# ramanPi_imagingBoard_ccdBoard.net
KiCad netlist of a schematic drawn in EAGLE
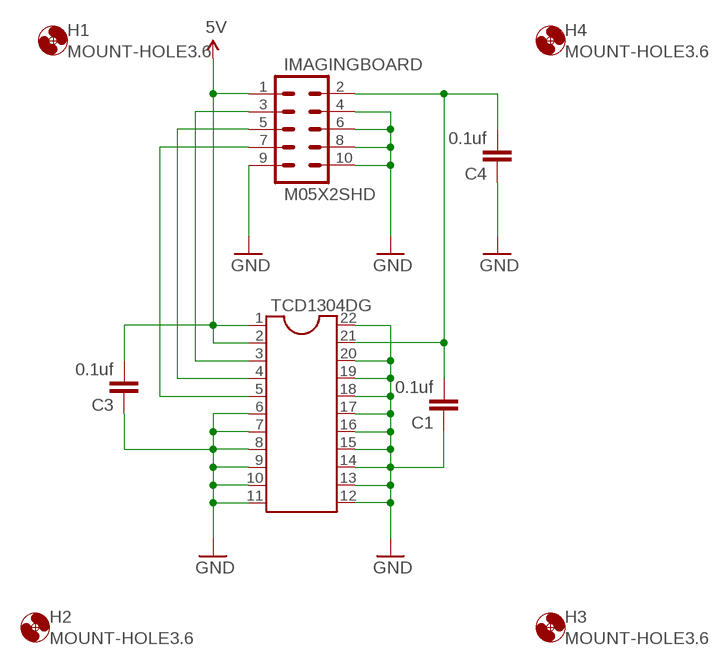
[diagram p0: schematic, sheet 1]

(export (version "E")
  (design (tool "Eeschema 10.0.6"))
  (components
    (comp (ref "C1")
      (value "0.1uf")
      (footprint "eagle-import:1210")
      (libsource (lib "eagle-import") (part "CAP1210"))
    )
    (comp (ref "C3")
      (value "0.1uf")
      (footprint "eagle-import:1210")
      (libsource (lib "eagle-import") (part "CAP1210"))
    )
    (comp (ref "C4")
      (value "0.1uf")
      (footprint "eagle-import:1210")
      (libsource (lib "eagle-import") (part "CAP1210"))
    )
    (comp (ref "H1")
      (value "MOUNT-HOLE3.6")
      (footprint "eagle-import:3,6")
      (libsource (lib "eagle-import") (part "MOUNT-HOLE3.6"))
    )
    (comp (ref "H2")
      (value "MOUNT-HOLE3.6")
      (footprint "eagle-import:3,6")
      (libsource (lib "eagle-import") (part "MOUNT-HOLE3.6"))
    )
    (comp (ref "H3")
      (value "MOUNT-HOLE3.6")
      (footprint "eagle-import:3,6")
      (libsource (lib "eagle-import") (part "MOUNT-HOLE3.6"))
    )
    (comp (ref "H4")
      (value "MOUNT-HOLE3.6")
      (footprint "eagle-import:3,6")
      (libsource (lib "eagle-import") (part "MOUNT-HOLE3.6"))
    )
    (comp (ref "IMAGINGBOARD")
      (value "M05X2SHD")
      (footprint "eagle-import:2X5-SHROUDED")
      (libsource (lib "eagle-import") (part "M05X2SHD"))
    )
    (comp (ref "TCD1304DG")
      (value "DIL22-4")
      (footprint "eagle-import:DIL22-4")
      (libsource (lib "eagle-import") (part "DIL22-4"))
    )
  )
  (nets
    (net (code "1") (name "5V") (class "Default")
      (node (ref "C3") (pin "2") (pinfunction "2_2") (pintype "passive"))
      (node (ref "IMAGINGBOARD") (pin "1") (pinfunction "1_1") (pintype "passive"))
      (node (ref "TCD1304DG") (pin "1") (pinfunction "1_1") (pintype "passive"))
      (node (ref "TCD1304DG") (pin "2") (pinfunction "2_2") (pintype "passive"))
    )
    (net (code "2") (name "GND") (class "Default")
      (node (ref "C1") (pin "1") (pinfunction "1_1") (pintype "passive"))
      (node (ref "C3") (pin "1") (pinfunction "1_1") (pintype "passive"))
      (node (ref "C4") (pin "1") (pinfunction "1_1") (pintype "passive"))
      (node (ref "IMAGINGBOARD") (pin "10") (pinfunction "10_10") (pintype "passive"))
      (node (ref "IMAGINGBOARD") (pin "4") (pinfunction "4_4") (pintype "passive"))
      (node (ref "IMAGINGBOARD") (pin "6") (pinfunction "6_6") (pintype "passive"))
      (node (ref "IMAGINGBOARD") (pin "8") (pinfunction "8_8") (pintype "passive"))
      (node (ref "IMAGINGBOARD") (pin "9") (pinfunction "9_9") (pintype "passive"))
      (node (ref "TCD1304DG") (pin "10") (pinfunction "10_10") (pintype "passive"))
      (node (ref "TCD1304DG") (pin "11") (pinfunction "11_11") (pintype "passive"))
      (node (ref "TCD1304DG") (pin "12") (pinfunction "12_12") (pintype "passive"))
      (node (ref "TCD1304DG") (pin "13") (pinfunction "13_13") (pintype "passive"))
      (node (ref "TCD1304DG") (pin "14") (pinfunction "14_14") (pintype "passive"))
      (node (ref "TCD1304DG") (pin "15") (pinfunction "15_15") (pintype "passive"))
      (node (ref "TCD1304DG") (pin "16") (pinfunction "16_16") (pintype "passive"))
      (node (ref "TCD1304DG") (pin "17") (pinfunction "17_17") (pintype "passive"))
      (node (ref "TCD1304DG") (pin "18") (pinfunction "18_18") (pintype "passive"))
      (node (ref "TCD1304DG") (pin "19") (pinfunction "19_19") (pintype "passive"))
      (node (ref "TCD1304DG") (pin "20") (pinfunction "20_20") (pintype "passive"))
      (node (ref "TCD1304DG") (pin "22") (pinfunction "22_22") (pintype "passive"))
      (node (ref "TCD1304DG") (pin "6") (pinfunction "6_6") (pintype "passive"))
      (node (ref "TCD1304DG") (pin "7") (pinfunction "7_7") (pintype "passive"))
      (node (ref "TCD1304DG") (pin "8") (pinfunction "8_8") (pintype "passive"))
      (node (ref "TCD1304DG") (pin "9") (pinfunction "9_9") (pintype "passive"))
    )
    (net (code "3") (name "Net-(C1-Pad2)") (class "Default")
      (node (ref "C1") (pin "2") (pinfunction "2_2") (pintype "passive"))
      (node (ref "C4") (pin "2") (pinfunction "2_2") (pintype "passive"))
      (node (ref "IMAGINGBOARD") (pin "2") (pinfunction "2_2") (pintype "passive"))
      (node (ref "TCD1304DG") (pin "21") (pinfunction "21_21") (pintype "passive"))
    )
    (net (code "4") (name "Net-(IMAGINGBOARD-Pad3)") (class "Default")
      (node (ref "IMAGINGBOARD") (pin "3") (pinfunction "3_3") (pintype "passive"))
      (node (ref "TCD1304DG") (pin "3") (pinfunction "3_3") (pintype "passive"))
    )
    (net (code "5") (name "Net-(IMAGINGBOARD-Pad5)") (class "Default")
      (node (ref "IMAGINGBOARD") (pin "5") (pinfunction "5_5") (pintype "passive"))
      (node (ref "TCD1304DG") (pin "4") (pinfunction "4_4") (pintype "passive"))
    )
    (net (code "6") (name "Net-(IMAGINGBOARD-Pad7)") (class "Default")
      (node (ref "IMAGINGBOARD") (pin "7") (pinfunction "7_7") (pintype "passive"))
      (node (ref "TCD1304DG") (pin "5") (pinfunction "5_5") (pintype "passive"))
    )
  )
)
